# RFLNA-14dB.net
KiCad netlist of a schematic drawn in Altium Designer
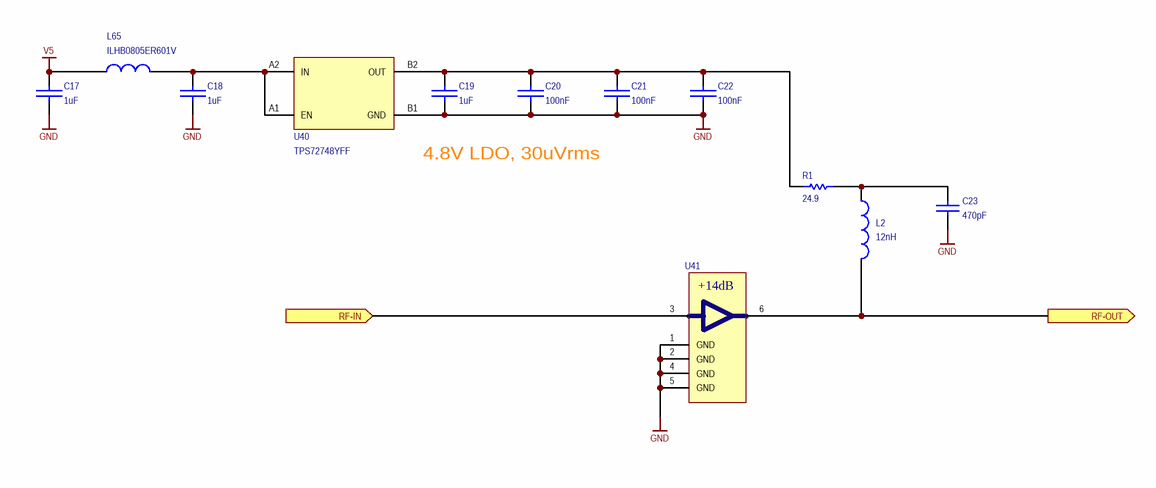
[diagram p0: RFLNA-14dB.SchDoc]

(export (version "E")
  (design (tool "Eeschema 10.0.6"))
  (components
    (comp (ref "C17")
      (value "1uF")
      (footprint "generic:0402")
      (description "Ceramic Capacitor 1uF ±10% 10V X5R 0402")
      (fields (field (name "MANUFACTURER") "Murata") (field (name "TOLERANCE") "±10%"))
      (libsource (lib "*") (part "CAP"))
    )
    (comp (ref "C18")
      (value "1uF")
      (footprint "generic:0402")
      (description "Ceramic Capacitor 1uF ±10% 10V X5R 0402")
      (fields (field (name "MANUFACTURER") "Murata") (field (name "TOLERANCE") "±10%"))
      (libsource (lib "*") (part "CAP"))
    )
    (comp (ref "C19")
      (value "1uF")
      (footprint "generic:0402")
      (description "Ceramic Capacitor 1uF ±10% 10V X5R 0402")
      (fields (field (name "MANUFACTURER") "Murata") (field (name "TOLERANCE") "±10%"))
      (libsource (lib "*") (part "CAP"))
    )
    (comp (ref "C20")
      (value "100nF")
      (footprint "generic:0402")
      (description "Ceramic Capacitor 100nF ±10% 16V X7R 0402")
      (fields (field (name "MANUFACTURER") "Murata") (field (name "VOLTAGE") "16V"))
      (libsource (lib "*") (part "CAP"))
    )
    (comp (ref "C21")
      (value "100nF")
      (footprint "generic:0402")
      (description "Ceramic Capacitor 100nF ±10% 16V X7R 0402")
      (fields (field (name "MANUFACTURER") "Murata") (field (name "VOLTAGE") "16V"))
      (libsource (lib "*") (part "CAP"))
    )
    (comp (ref "C22")
      (value "100nF")
      (footprint "generic:0402")
      (description "Ceramic Capacitor 100nF ±10% 16V X7R 0402")
      (fields (field (name "MANUFACTURER") "Murata") (field (name "VOLTAGE") "16V"))
      (libsource (lib "*") (part "CAP"))
    )
    (comp (ref "C23")
      (value "470pF")
      (footprint "generic:0402")
      (description "Ceramic Capacitor 470pF ±5% 50V NP0 0402")
      (fields (field (name "VOLTAGE") "50V") (field (name "MANUFACTURER") "Murata"))
      (libsource (lib "Graviton") (part "CAP 0402"))
    )
    (comp (ref "L2")
      (value "12nH")
      (footprint "0402")
      (description "Inductor Wirewound 12nH ±5% 0402")
      (fields (field (name "MANUFACTURER") "Murata") (field (name "TOLERANCE") "±5%"))
      (libsource (lib "generic") (part "INDUCTOR"))
    )
    (comp (ref "L65")
      (value "ILHB0805ER601V")
      (footprint "0805")
      (description "Ferrite Bead 600-Ohm @ 100MHz 2A 0805")
      (fields (field (name "MANUFACTURER") "Vishay Dale") (field (name "TOLERANCE") "±25%"))
      (libsource (lib "*") (part "INDUCTANCE1"))
    )
    (comp (ref "R1")
      (value "24.9")
      (footprint "generic:0603")
      (description "Thick Film Resistor 24.9 ±1% 0603")
      (fields (field (name "MANUFACTURER") "Panasonic") (field (name "TOLERANCE") "±1%"))
      (libsource (lib "Graviton") (part "RES 0603"))
    )
    (comp (ref "U40")
      (value "TPS72748YFF")
      (footprint "DSBGA-4")
      (description "Ultralow Noise 30uVrms LDO, Fixed, 4.8V, 200mA")
      (fields
        (field (name "MANUFACTURER P/N") "TPS72748YFF")
        (field (name "MANUFACTURER") "Texas Instruments")
      )
      (libsource (lib "ti") (part "TPS72748YFF"))
    )
    (comp (ref "U41")
      (value "MAAL-009120")
      (footprint "SC70")
      (description "Broadband 14dB 70-3000MHz Gain Stage")
      (fields (field (name "MANUFACTURER") "Macom"))
      (libsource (lib "macom") (part "MAAL-009120"))
    )
  )
  (nets
    (net (code "1") (name "/RF-IN") (class "Default")
      (node (ref "U41") (pin "3") (pinfunction "RF-IN_3") (pintype "passive"))
    )
    (net (code "2") (name "/RF-OUT") (class "Default")
      (node (ref "L2") (pin "2") (pinfunction "2_2") (pintype "passive"))
      (node (ref "U41") (pin "6") (pinfunction "RF-OUT_6") (pintype "passive"))
    )
    (net (code "3") (name "GND") (class "Default")
      (node (ref "C17") (pin "1") (pinfunction "1_1") (pintype "passive"))
      (node (ref "C18") (pin "1") (pinfunction "1_1") (pintype "passive"))
      (node (ref "C19") (pin "1") (pinfunction "1_1") (pintype "passive"))
      (node (ref "C20") (pin "1") (pinfunction "1_1") (pintype "passive"))
      (node (ref "C21") (pin "1") (pinfunction "1_1") (pintype "passive"))
      (node (ref "C22") (pin "1") (pinfunction "1_1") (pintype "passive"))
      (node (ref "C23") (pin "1") (pinfunction "1_1") (pintype "passive"))
      (node (ref "U40") (pin "B1") (pinfunction "GND_B1") (pintype "passive"))
      (node (ref "U41") (pin "1") (pinfunction "GND_1") (pintype "passive"))
      (node (ref "U41") (pin "2") (pinfunction "GND_2") (pintype "passive"))
      (node (ref "U41") (pin "4") (pinfunction "GND_4") (pintype "passive"))
      (node (ref "U41") (pin "5") (pinfunction "GND_5") (pintype "passive"))
    )
    (net (code "4") (name "Net-(C23-Pad2)") (class "Default")
      (node (ref "C23") (pin "2") (pinfunction "2_2") (pintype "passive"))
      (node (ref "L2") (pin "1") (pinfunction "1_1") (pintype "passive"))
      (node (ref "R1") (pin "2") (pinfunction "2_2") (pintype "passive"))
    )
    (net (code "5") (name "Net-(U40-EN)") (class "Default")
      (node (ref "C18") (pin "2") (pinfunction "2_2") (pintype "passive"))
      (node (ref "L65") (pin "1") (pinfunction "1_1") (pintype "passive"))
      (node (ref "U40") (pin "A1") (pinfunction "EN_A1") (pintype "passive"))
      (node (ref "U40") (pin "A2") (pinfunction "IN_A2") (pintype "passive"))
    )
    (net (code "6") (name "Net-(U40-OUT)") (class "Default")
      (node (ref "C19") (pin "2") (pinfunction "2_2") (pintype "passive"))
      (node (ref "C20") (pin "2") (pinfunction "2_2") (pintype "passive"))
      (node (ref "C21") (pin "2") (pinfunction "2_2") (pintype "passive"))
      (node (ref "C22") (pin "2") (pinfunction "2_2") (pintype "passive"))
      (node (ref "R1") (pin "1") (pinfunction "1_1") (pintype "passive"))
      (node (ref "U40") (pin "B2") (pinfunction "OUT_B2") (pintype "passive"))
    )
    (net (code "7") (name "V5") (class "Default")
      (node (ref "C17") (pin "2") (pinfunction "2_2") (pintype "passive"))
      (node (ref "L65") (pin "2") (pinfunction "2_2") (pintype "passive"))
    )
  )
)
